# 1-Schematic_SPL_Watermelon_Elektrobox.net
KiCad netlist of a schematic drawn in EasyEDA
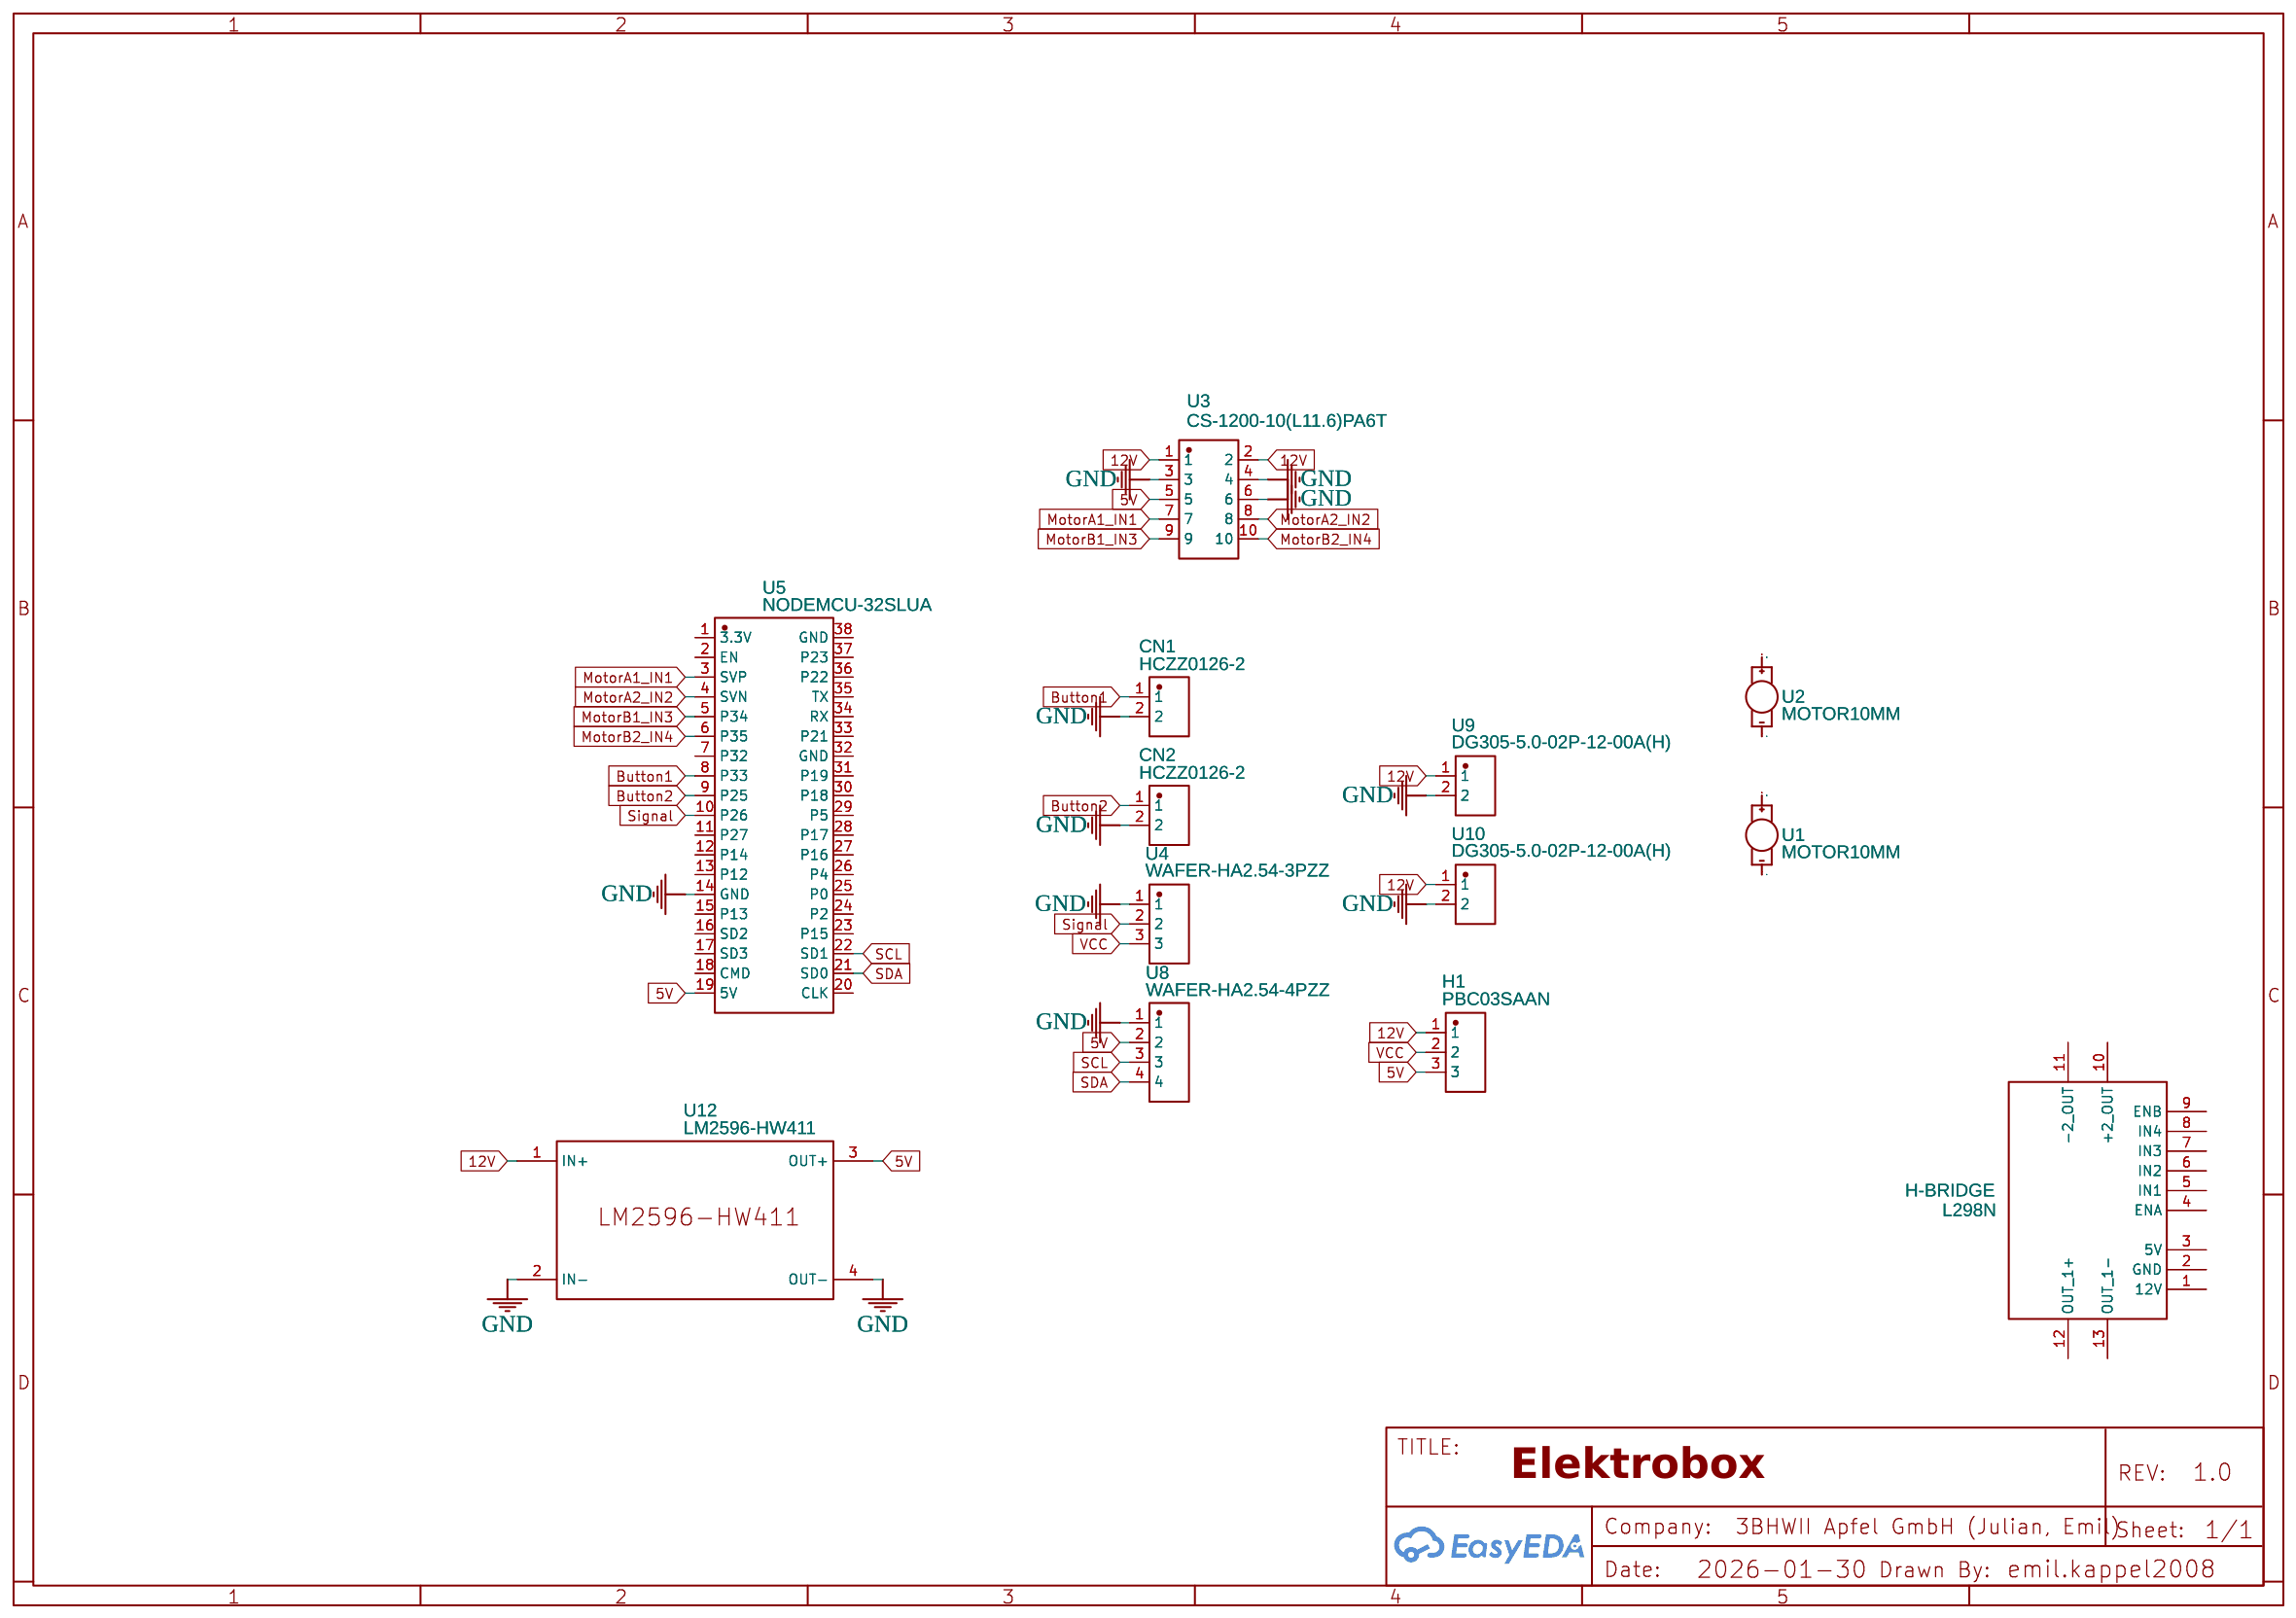
[diagram p0: schematic sheet]

(export (version "E")
  (design (tool "Eeschema 10.0.6"))
  (components
    (comp (ref "CN1")
      (value "HCZZ0126-2")
      (fields (field (name "Manufacturer") "HC(虹成电子)"))
      (libsource (lib "") (part "HCZZ0126-2"))
    )
    (comp (ref "CN2")
      (value "HCZZ0126-2")
      (fields (field (name "Manufacturer") "HC(虹成电子)"))
      (libsource (lib "") (part "HCZZ0126-2"))
    )
    (comp (ref "H-BRIDGE")
      (value "L298N")
      (libsource (lib "") (part "L298N DUAL H-BRIDGE MOTOR DRIVER MODULE"))
    )
    (comp (ref "H1")
      (value "PBC03SAAN")
      (fields (field (name "Manufacturer") "Sullins"))
      (libsource (lib "") (part "PBC03SAAN"))
    )
    (comp (ref "U1") (value "MOTOR10MM") (libsource (lib "") (part "MOTOR10MM")))
    (comp (ref "U2") (value "MOTOR10MM") (libsource (lib "") (part "MOTOR10MM")))
    (comp (ref "U3")
      (value "CS-1200-10(L11.6)PA6T")
      (fields (field (name "Manufacturer") "CST(永丰盈)"))
      (libsource (lib "") (part "CS-1200-10(L11.6)PA6T"))
    )
    (comp (ref "U4")
      (value "WAFER-HA2.54-3PZZ")
      (fields (field (name "Manufacturer") "XUNPU(讯普)"))
      (libsource (lib "") (part "WAFER-HA2.54-3PZZ"))
    )
    (comp (ref "U5")
      (value "NODEMCU-32SLUA")
      (fields
        (field (name "Manufacturer Part") "NodeMCU-32SLua")
        (field (name "Manufacturer") "Ai-Thinker(安信可)")
      )
      (libsource (lib "") (part "NODEMCU-32SLUA"))
    )
    (comp (ref "U8")
      (value "WAFER-HA2.54-4PZZ")
      (fields (field (name "Manufacturer") "XUNPU(讯普)"))
      (libsource (lib "") (part "WAFER-HA2.54-4PZZ"))
    )
    (comp (ref "U9")
      (value "DG305-5.0-02P-12-00A(H)")
      (fields (field (name "Manufacturer") "DEGSON(高正/高松)"))
      (libsource (lib "") (part "DG305-5.0-02P-12-00A(H)"))
    )
    (comp (ref "U10")
      (value "DG305-5.0-02P-12-00A(H)")
      (fields (field (name "Manufacturer") "DEGSON(高正/高松)"))
      (libsource (lib "") (part "DG305-5.0-02P-12-00A(H)"))
    )
    (comp (ref "U12") (value "LM2596-HW411") (libsource (lib "") (part "LM2596-HW411")))
  )
  (nets
    (net (code "1") (name "5V") (class "Default")
      (node (ref "H1") (pin "3") (pinfunction "3_3") (pintype "unspecified"))
      (node (ref "U12") (pin "3") (pinfunction "OUT+_3") (pintype "unspecified"))
      (node (ref "U3") (pin "5") (pinfunction "5_5") (pintype "unspecified"))
      (node (ref "U5") (pin "19") (pinfunction "5V_19") (pintype "unspecified"))
      (node (ref "U8") (pin "2") (pinfunction "2_2") (pintype "unspecified"))
    )
    (net (code "2") (name "12V") (class "Default")
      (node (ref "H1") (pin "1") (pinfunction "1_1") (pintype "unspecified"))
      (node (ref "U10") (pin "1") (pinfunction "1_1") (pintype "unspecified"))
      (node (ref "U12") (pin "1") (pinfunction "IN+_1") (pintype "unspecified"))
      (node (ref "U3") (pin "1") (pinfunction "1_1") (pintype "unspecified"))
      (node (ref "U3") (pin "2") (pinfunction "2_2") (pintype "unspecified"))
      (node (ref "U9") (pin "1") (pinfunction "1_1") (pintype "unspecified"))
    )
    (net (code "3") (name "Button1") (class "Default")
      (node (ref "CN1") (pin "1") (pinfunction "1_1") (pintype "unspecified"))
      (node (ref "U5") (pin "8") (pinfunction "P33_8") (pintype "unspecified"))
    )
    (net (code "4") (name "Button2") (class "Default")
      (node (ref "CN2") (pin "1") (pinfunction "1_1") (pintype "unspecified"))
      (node (ref "U5") (pin "9") (pinfunction "P25_9") (pintype "unspecified"))
    )
    (net (code "5") (name "GND") (class "Default")
      (node (ref "CN1") (pin "2") (pinfunction "2_2") (pintype "unspecified"))
      (node (ref "CN2") (pin "2") (pinfunction "2_2") (pintype "unspecified"))
      (node (ref "U10") (pin "2") (pinfunction "2_2") (pintype "unspecified"))
      (node (ref "U12") (pin "2") (pinfunction "IN-_2") (pintype "unspecified"))
      (node (ref "U12") (pin "4") (pinfunction "OUT-_4") (pintype "unspecified"))
      (node (ref "U3") (pin "3") (pinfunction "3_3") (pintype "unspecified"))
      (node (ref "U3") (pin "4") (pinfunction "4_4") (pintype "unspecified"))
      (node (ref "U3") (pin "6") (pinfunction "6_6") (pintype "unspecified"))
      (node (ref "U4") (pin "1") (pinfunction "1_1") (pintype "unspecified"))
      (node (ref "U5") (pin "14") (pinfunction "GND_14") (pintype "unspecified"))
      (node (ref "U8") (pin "1") (pinfunction "1_1") (pintype "unspecified"))
      (node (ref "U9") (pin "2") (pinfunction "2_2") (pintype "unspecified"))
    )
    (net (code "6") (name "MotorA1_IN1") (class "Default")
      (node (ref "U3") (pin "7") (pinfunction "7_7") (pintype "unspecified"))
      (node (ref "U5") (pin "3") (pinfunction "SVP_3") (pintype "unspecified"))
    )
    (net (code "7") (name "MotorA2_IN2") (class "Default")
      (node (ref "U3") (pin "8") (pinfunction "8_8") (pintype "unspecified"))
      (node (ref "U5") (pin "4") (pinfunction "SVN_4") (pintype "unspecified"))
    )
    (net (code "8") (name "MotorB1_IN3") (class "Default")
      (node (ref "U3") (pin "9") (pinfunction "9_9") (pintype "unspecified"))
      (node (ref "U5") (pin "5") (pinfunction "P34_5") (pintype "unspecified"))
    )
    (net (code "9") (name "MotorB2_IN4") (class "Default")
      (node (ref "U3") (pin "10") (pinfunction "10_10") (pintype "unspecified"))
      (node (ref "U5") (pin "6") (pinfunction "P35_6") (pintype "unspecified"))
    )
    (net (code "10") (name "SCL") (class "Default")
      (node (ref "U5") (pin "22") (pinfunction "SD1_22") (pintype "unspecified"))
      (node (ref "U8") (pin "3") (pinfunction "3_3") (pintype "unspecified"))
    )
    (net (code "11") (name "SDA") (class "Default")
      (node (ref "U5") (pin "21") (pinfunction "SD0_21") (pintype "unspecified"))
      (node (ref "U8") (pin "4") (pinfunction "4_4") (pintype "unspecified"))
    )
    (net (code "12") (name "Signal") (class "Default")
      (node (ref "U4") (pin "2") (pinfunction "2_2") (pintype "unspecified"))
      (node (ref "U5") (pin "10") (pinfunction "P26_10") (pintype "unspecified"))
    )
    (net (code "13") (name "VCC") (class "Default")
      (node (ref "H1") (pin "2") (pinfunction "2_2") (pintype "unspecified"))
      (node (ref "U4") (pin "3") (pinfunction "3_3") (pintype "unspecified"))
    )
    (net (code "14") (name "unconnected-(H-BRIDGE-+2_OUT-Pad10)") (class "Default")
      (node (ref "H-BRIDGE") (pin "10") (pinfunction "+2_OUT_10") (pintype "output"))
    )
    (net (code "15") (name "unconnected-(H-BRIDGE--2_OUT-Pad11)") (class "Default")
      (node (ref "H-BRIDGE") (pin "11") (pinfunction "-2_OUT_11") (pintype "output"))
    )
    (net (code "16") (name "unconnected-(H-BRIDGE-5V-Pad3)") (class "Default")
      (node (ref "H-BRIDGE") (pin "3") (pinfunction "5V_3") (pintype "passive"))
    )
    (net (code "17") (name "unconnected-(H-BRIDGE-12V-Pad1)") (class "Default")
      (node (ref "H-BRIDGE") (pin "1") (pinfunction "12V_1") (pintype "passive"))
    )
    (net (code "18") (name "unconnected-(H-BRIDGE-ENA-Pad4)") (class "Default")
      (node (ref "H-BRIDGE") (pin "4") (pinfunction "ENA_4") (pintype "input"))
    )
    (net (code "19") (name "unconnected-(H-BRIDGE-ENB-Pad9)") (class "Default")
      (node (ref "H-BRIDGE") (pin "9") (pinfunction "ENB_9") (pintype "input"))
    )
    (net (code "20") (name "unconnected-(H-BRIDGE-GND-Pad2)") (class "Default")
      (node (ref "H-BRIDGE") (pin "2") (pinfunction "GND_2") (pintype "passive"))
    )
    (net (code "21") (name "unconnected-(H-BRIDGE-IN1-Pad5)") (class "Default")
      (node (ref "H-BRIDGE") (pin "5") (pinfunction "IN1_5") (pintype "input"))
    )
    (net (code "22") (name "unconnected-(H-BRIDGE-IN2-Pad6)") (class "Default")
      (node (ref "H-BRIDGE") (pin "6") (pinfunction "IN2_6") (pintype "input"))
    )
    (net (code "23") (name "unconnected-(H-BRIDGE-IN3-Pad7)") (class "Default")
      (node (ref "H-BRIDGE") (pin "7") (pinfunction "IN3_7") (pintype "input"))
    )
    (net (code "24") (name "unconnected-(H-BRIDGE-IN4-Pad8)") (class "Default")
      (node (ref "H-BRIDGE") (pin "8") (pinfunction "IN4_8") (pintype "input"))
    )
    (net (code "25") (name "unconnected-(H-BRIDGE-OUT_1+-Pad12)") (class "Default")
      (node (ref "H-BRIDGE") (pin "12") (pinfunction "OUT_1+_12") (pintype "output"))
    )
    (net (code "26") (name "unconnected-(H-BRIDGE-OUT_1--Pad13)") (class "Default")
      (node (ref "H-BRIDGE") (pin "13") (pinfunction "OUT_1-_13") (pintype "output"))
    )
    (net (code "27") (name "unconnected-(U1-Pad+)") (class "Default")
      (node (ref "U1") (pin "+") (pinfunction "+_+") (pintype "unspecified"))
    )
    (net (code "28") (name "unconnected-(U1-Pad-)") (class "Default")
      (node (ref "U1") (pin "-") (pinfunction "-_-") (pintype "unspecified"))
    )
    (net (code "29") (name "unconnected-(U2-Pad+)") (class "Default")
      (node (ref "U2") (pin "+") (pinfunction "+_+") (pintype "unspecified"))
    )
    (net (code "30") (name "unconnected-(U2-Pad-)") (class "Default")
      (node (ref "U2") (pin "-") (pinfunction "-_-") (pintype "unspecified"))
    )
    (net (code "31") (name "unconnected-(U5-3.3V-Pad1)") (class "Default")
      (node (ref "U5") (pin "1") (pinfunction "3.3V_1") (pintype "unspecified"))
    )
    (net (code "32") (name "unconnected-(U5-CLK-Pad20)") (class "Default")
      (node (ref "U5") (pin "20") (pinfunction "CLK_20") (pintype "unspecified"))
    )
    (net (code "33") (name "unconnected-(U5-CMD-Pad18)") (class "Default")
      (node (ref "U5") (pin "18") (pinfunction "CMD_18") (pintype "unspecified"))
    )
    (net (code "34") (name "unconnected-(U5-EN-Pad2)") (class "Default")
      (node (ref "U5") (pin "2") (pinfunction "EN_2") (pintype "unspecified"))
    )
    (net (code "35") (name "unconnected-(U5-GND-Pad32)") (class "Default")
      (node (ref "U5") (pin "32") (pinfunction "GND_32") (pintype "unspecified"))
    )
    (net (code "36") (name "unconnected-(U5-GND-Pad38)") (class "Default")
      (node (ref "U5") (pin "38") (pinfunction "GND_38") (pintype "unspecified"))
    )
    (net (code "37") (name "unconnected-(U5-P0-Pad25)") (class "Default")
      (node (ref "U5") (pin "25") (pinfunction "P0_25") (pintype "unspecified"))
    )
    (net (code "38") (name "unconnected-(U5-P2-Pad24)") (class "Default")
      (node (ref "U5") (pin "24") (pinfunction "P2_24") (pintype "unspecified"))
    )
    (net (code "39") (name "unconnected-(U5-P4-Pad26)") (class "Default")
      (node (ref "U5") (pin "26") (pinfunction "P4_26") (pintype "unspecified"))
    )
    (net (code "40") (name "unconnected-(U5-P5-Pad29)") (class "Default")
      (node (ref "U5") (pin "29") (pinfunction "P5_29") (pintype "unspecified"))
    )
    (net (code "41") (name "unconnected-(U5-P12-Pad13)") (class "Default")
      (node (ref "U5") (pin "13") (pinfunction "P12_13") (pintype "unspecified"))
    )
    (net (code "42") (name "unconnected-(U5-P13-Pad15)") (class "Default")
      (node (ref "U5") (pin "15") (pinfunction "P13_15") (pintype "unspecified"))
    )
    (net (code "43") (name "unconnected-(U5-P14-Pad12)") (class "Default")
      (node (ref "U5") (pin "12") (pinfunction "P14_12") (pintype "unspecified"))
    )
    (net (code "44") (name "unconnected-(U5-P15-Pad23)") (class "Default")
      (node (ref "U5") (pin "23") (pinfunction "P15_23") (pintype "unspecified"))
    )
    (net (code "45") (name "unconnected-(U5-P16-Pad27)") (class "Default")
      (node (ref "U5") (pin "27") (pinfunction "P16_27") (pintype "unspecified"))
    )
    (net (code "46") (name "unconnected-(U5-P17-Pad28)") (class "Default")
      (node (ref "U5") (pin "28") (pinfunction "P17_28") (pintype "unspecified"))
    )
    (net (code "47") (name "unconnected-(U5-P18-Pad30)") (class "Default")
      (node (ref "U5") (pin "30") (pinfunction "P18_30") (pintype "unspecified"))
    )
    (net (code "48") (name "unconnected-(U5-P19-Pad31)") (class "Default")
      (node (ref "U5") (pin "31") (pinfunction "P19_31") (pintype "unspecified"))
    )
    (net (code "49") (name "unconnected-(U5-P21-Pad33)") (class "Default")
      (node (ref "U5") (pin "33") (pinfunction "P21_33") (pintype "unspecified"))
    )
    (net (code "50") (name "unconnected-(U5-P22-Pad36)") (class "Default")
      (node (ref "U5") (pin "36") (pinfunction "P22_36") (pintype "unspecified"))
    )
    (net (code "51") (name "unconnected-(U5-P23-Pad37)") (class "Default")
      (node (ref "U5") (pin "37") (pinfunction "P23_37") (pintype "unspecified"))
    )
    (net (code "52") (name "unconnected-(U5-P27-Pad11)") (class "Default")
      (node (ref "U5") (pin "11") (pinfunction "P27_11") (pintype "unspecified"))
    )
    (net (code "53") (name "unconnected-(U5-P32-Pad7)") (class "Default")
      (node (ref "U5") (pin "7") (pinfunction "P32_7") (pintype "unspecified"))
    )
    (net (code "54") (name "unconnected-(U5-RX-Pad34)") (class "Default")
      (node (ref "U5") (pin "34") (pinfunction "RX_34") (pintype "unspecified"))
    )
    (net (code "55") (name "unconnected-(U5-SD2-Pad16)") (class "Default")
      (node (ref "U5") (pin "16") (pinfunction "SD2_16") (pintype "unspecified"))
    )
    (net (code "56") (name "unconnected-(U5-SD3-Pad17)") (class "Default")
      (node (ref "U5") (pin "17") (pinfunction "SD3_17") (pintype "unspecified"))
    )
    (net (code "57") (name "unconnected-(U5-TX-Pad35)") (class "Default")
      (node (ref "U5") (pin "35") (pinfunction "TX_35") (pintype "unspecified"))
    )
  )
)
